# Comparator.net
KiCad netlist of a schematic drawn in Altium Designer
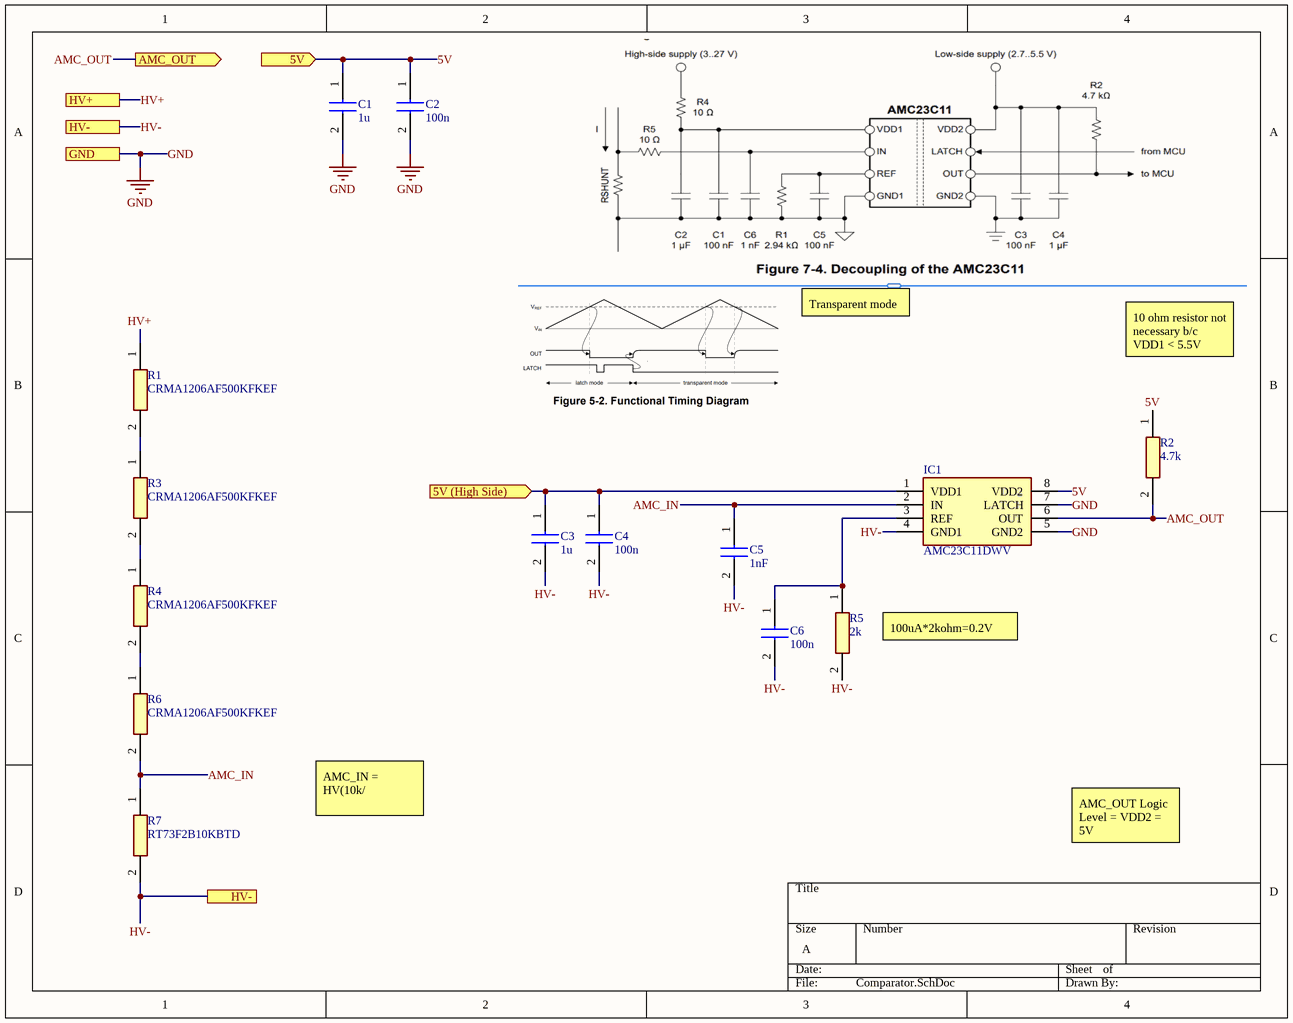
[diagram p0: Comparator.SchDoc]

(export (version "E")
  (design (tool "Eeschema 10.0.6"))
  (components
    (comp (ref "C1")
      (value "1u")
      (footprint "SamacSys:CAPC2012X145N")
      (description "Capacitor")
      (fields (field (name "MANUFACTURER_PART_NUMBER") "KGM21AV51H105ZU"))
      (libsource (lib "SamacSys") (part "KGM21AV51H105ZU"))
    )
    (comp (ref "C2")
      (value "100n")
      (footprint "SamacSys:CAPC2012X147N")
      (description "Capacitor")
      (fields
        (field (name "MANUFACTURER_PART_NUMBER") "KGF21BR71H104KT")
        (field (name "MOUSER PART NUMBER") "581-KGF21BR71H104KT")
      )
      (libsource (lib "SamacSys") (part "KGF21BR71H104KT"))
    )
    (comp (ref "C3")
      (value "1u")
      (footprint "SamacSys:CAPC2012X145N")
      (description "Capacitor")
      (fields (field (name "MANUFACTURER_PART_NUMBER") "KGM21AV51H105ZU"))
      (libsource (lib "SamacSys") (part "KGM21AV51H105ZU"))
    )
    (comp (ref "C4")
      (value "100n")
      (footprint "SamacSys:CAPC2012X147N")
      (description "Capacitor")
      (fields
        (field (name "MANUFACTURER_PART_NUMBER") "KGF21BR71H104KT")
        (field (name "MOUSER PART NUMBER") "581-KGF21BR71H104KT")
      )
      (libsource (lib "SamacSys") (part "KGF21BR71H104KT"))
    )
    (comp (ref "C5")
      (value "1nF")
      (footprint "SamacSys:C1210")
      (description "Capacitor")
      (fields
        (field (name "MANUFACTURER_PART_NUMBER") "C1210C102JDGACAUTO")
        (field (name "MOUSER PART NUMBER") "80-C1210C102JDGAUTO")
      )
      (libsource (lib "SamacSys") (part "C1210C102JDGACAUTO"))
    )
    (comp (ref "C6")
      (value "100n")
      (footprint "SamacSys:CAPC2012X147N")
      (description "Capacitor")
      (fields
        (field (name "MANUFACTURER_PART_NUMBER") "KGF21BR71H104KT")
        (field (name "MOUSER PART NUMBER") "581-KGF21BR71H104KT")
      )
      (libsource (lib "SamacSys") (part "KGF21BR71H104KT"))
    )
    (comp (ref "IC1")
      (value "AMC23C11DWV")
      (footprint "SamacSys:SOIC127P1150X280-8N")
      (description "Integrated Circuit")
      (fields (field (name "MOUSER PART NUMBER") "595-AMC23C11DWV"))
      (libsource (lib "SamacSys") (part "AMC23C11DWV"))
    )
    (comp (ref "R1")
      (value "CRMA1206AF500KFKEF")
      (footprint "RESC3216X74N")
      (description "Resistor")
      (fields (field (name "MOUSER PART NUMBER") "71-CRMA1206AF500KFKF"))
      (libsource (lib "SamacSys") (part "CRMA1206AF500KFKEF"))
    )
    (comp (ref "R2")
      (value "4.7k")
      (footprint "SamacSys:RESC2012X65N")
      (description "Resistor")
      (fields
        (field (name "MANUFACTURER_PART_NUMBER") "CRG0805J4K7")
        (field (name "MOUSER PART NUMBER") "279-CRG0805J4K7")
      )
      (libsource (lib "SamacSys") (part "CRG0805J4K7"))
    )
    (comp (ref "R3")
      (value "CRMA1206AF500KFKEF")
      (footprint "RESC3216X74N")
      (description "Resistor")
      (fields (field (name "MOUSER PART NUMBER") "71-CRMA1206AF500KFKF"))
      (libsource (lib "SamacSys") (part "CRMA1206AF500KFKEF"))
    )
    (comp (ref "R4")
      (value "CRMA1206AF500KFKEF")
      (footprint "RESC3216X74N")
      (description "Resistor")
      (fields (field (name "MOUSER PART NUMBER") "71-CRMA1206AF500KFKF"))
      (libsource (lib "SamacSys") (part "CRMA1206AF500KFKEF"))
    )
    (comp (ref "R5")
      (value "2k")
      (footprint "SamacSys:ERJP06D1000V")
      (description "Resistor")
      (fields
        (field (name "MANUFACTURER_PART_NUMBER") "ERJ-P06F2001V")
        (field (name "MOUSER PART NUMBER") "667-ERJ-P06F2001V")
      )
      (libsource (lib "SamacSys") (part "ERJ-P06F2001V"))
    )
    (comp (ref "R6")
      (value "CRMA1206AF500KFKEF")
      (footprint "RESC3216X74N")
      (description "Resistor")
      (fields (field (name "MOUSER PART NUMBER") "71-CRMA1206AF500KFKF"))
      (libsource (lib "SamacSys") (part "CRMA1206AF500KFKEF"))
    )
    (comp (ref "R7")
      (value "RT73F2B10KBTD")
      (footprint "SamacSys:RESC3216X70N")
      (description "Resistor")
      (libsource (lib "SamacSys") (part "RT73F2B10KBTD"))
    )
  )
  (nets
    (net (code "1") (name "/5V") (class "Default")
      (node (ref "C1") (pin "1") (pinfunction "1_1") (pintype "passive"))
      (node (ref "C2") (pin "1") (pinfunction "1_1") (pintype "passive"))
      (node (ref "IC1") (pin "8") (pinfunction "VDD2_8") (pintype "passive"))
      (node (ref "R2") (pin "1") (pinfunction "1_1") (pintype "passive"))
    )
    (net (code "2") (name "/5V (High Side)") (class "Default")
      (node (ref "C3") (pin "1") (pinfunction "1_1") (pintype "passive"))
      (node (ref "C4") (pin "1") (pinfunction "1_1") (pintype "passive"))
      (node (ref "IC1") (pin "1") (pinfunction "VDD1_1") (pintype "passive"))
    )
    (net (code "3") (name "/AMC_IN") (class "Default")
      (node (ref "C5") (pin "1") (pinfunction "1_1") (pintype "passive"))
      (node (ref "IC1") (pin "2") (pinfunction "IN_2") (pintype "passive"))
      (node (ref "R6") (pin "2") (pinfunction "2_2") (pintype "passive"))
      (node (ref "R7") (pin "1") (pinfunction "1_1") (pintype "passive"))
    )
    (net (code "4") (name "/AMC_OUT") (class "Default")
      (node (ref "IC1") (pin "6") (pinfunction "OUT_6") (pintype "passive"))
      (node (ref "R2") (pin "2") (pinfunction "2_2") (pintype "passive"))
    )
    (net (code "5") (name "/HV+") (class "Default")
      (node (ref "R1") (pin "1") (pinfunction "1_1") (pintype "passive"))
    )
    (net (code "6") (name "/HV-") (class "Default")
      (node (ref "C3") (pin "2") (pinfunction "2_2") (pintype "passive"))
      (node (ref "C4") (pin "2") (pinfunction "2_2") (pintype "passive"))
      (node (ref "C5") (pin "2") (pinfunction "2_2") (pintype "passive"))
      (node (ref "C6") (pin "2") (pinfunction "2_2") (pintype "passive"))
      (node (ref "IC1") (pin "4") (pinfunction "GND1_4") (pintype "passive"))
      (node (ref "R5") (pin "2") (pinfunction "2_2") (pintype "passive"))
      (node (ref "R7") (pin "2") (pinfunction "2_2") (pintype "passive"))
    )
    (net (code "7") (name "GND") (class "Default")
      (node (ref "C1") (pin "2") (pinfunction "2_2") (pintype "passive"))
      (node (ref "C2") (pin "2") (pinfunction "2_2") (pintype "passive"))
      (node (ref "IC1") (pin "5") (pinfunction "GND2_5") (pintype "passive"))
      (node (ref "IC1") (pin "7") (pinfunction "LATCH_7") (pintype "passive"))
    )
    (net (code "8") (name "Net-(IC1-REF)") (class "Default")
      (node (ref "C6") (pin "1") (pinfunction "1_1") (pintype "passive"))
      (node (ref "IC1") (pin "3") (pinfunction "REF_3") (pintype "passive"))
      (node (ref "R5") (pin "1") (pinfunction "1_1") (pintype "passive"))
    )
    (net (code "9") (name "Net-(R1-Pad2)") (class "Default")
      (node (ref "R1") (pin "2") (pinfunction "2_2") (pintype "passive"))
      (node (ref "R3") (pin "1") (pinfunction "1_1") (pintype "passive"))
    )
    (net (code "10") (name "Net-(R3-Pad2)") (class "Default")
      (node (ref "R3") (pin "2") (pinfunction "2_2") (pintype "passive"))
      (node (ref "R4") (pin "1") (pinfunction "1_1") (pintype "passive"))
    )
    (net (code "11") (name "Net-(R4-Pad2)") (class "Default")
      (node (ref "R4") (pin "2") (pinfunction "2_2") (pintype "passive"))
      (node (ref "R6") (pin "1") (pinfunction "1_1") (pintype "passive"))
    )
  )
)
